# Memory_256M.net
KiCad netlist of a schematic drawn in Altium Designer
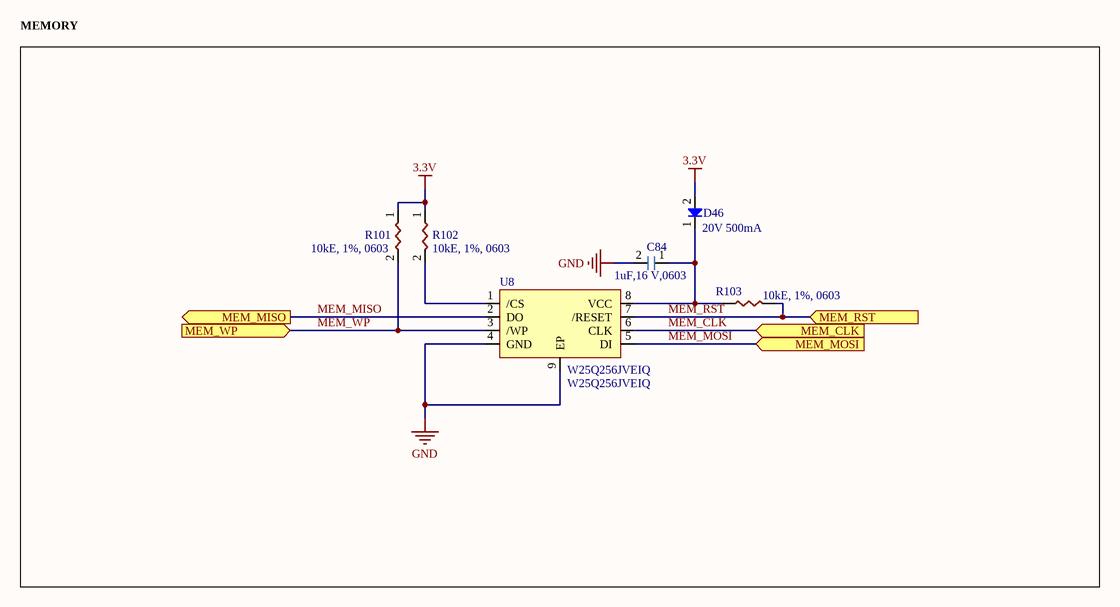
[diagram p0: Memory_256M.SchDoc]

(export (version "E")
  (design (tool "Eeschema 10.0.6"))
  (components
    (comp (ref "C84")
      (value "CGA3E1X7R1C105K080AC")
      (footprint "CAPC1608X05N 0603")
      (description "Multilayer Ceramic Capacitor, 1uF, 16V, ±10%,  X7R 0603 [1608 Metric]")
      (fields
        (field (name "MANUFACTURER") "TDK Corporation")
        (field (name "VOLTAGE") "16V")
        (field (name "VALUE DISPLAY") "1uF,16 V,0603")
      )
      (libsource (lib "BMS_V2.1_Adv") (part "Cap_CGA3E1X7R1C105K080AC"))
    )
    (comp (ref "D46")
      (value "SBR80520LT1G")
      (footprint "DIODE_SOD123")
      (description "Diode 20 V 500mA Surface Mount SOD-123")
      (fields
        (field (name "MANUFACTURER") "OnSemi")
        (field (name "VALUE DISPLAY") "20V 500mA")
        (field (name "VOLTAGE") "20V")
      )
      (libsource (lib "BMS_V2.1_Adv") (part "Diode_SBR80520LT1G"))
    )
    (comp (ref "R101")
      (value "CRCW060310K0FKEA")
      (footprint "RESC1608X05N 0603")
      (description "SMD Chip Resistor, 10 kOhm,±1%, 100 mW, 0603 [1608 Metric], Thick Film, General Purpose")
      (fields
        (field (name "MANUFACTURER") "Vishay Dale")
        (field (name "POWER") "1/10W")
        (field (name "VALUE DISPLAY") "10kE, 1%, 0603")
      )
      (libsource (lib "BMS_V2.1_Adv") (part "Res_CRCW060310K0FKEA"))
    )
    (comp (ref "R102")
      (value "CRCW060310K0FKEA")
      (footprint "RESC1608X05N 0603")
      (description "SMD Chip Resistor, 10 kOhm,±1%, 100 mW, 0603 [1608 Metric], Thick Film, General Purpose")
      (fields
        (field (name "MANUFACTURER") "Vishay Dale")
        (field (name "POWER") "1/10W")
        (field (name "VALUE DISPLAY") "10kE, 1%, 0603")
      )
      (libsource (lib "BMS_V2.1_Adv") (part "Res_CRCW060310K0FKEA"))
    )
    (comp (ref "R103")
      (value "CRCW060310K0FKEA")
      (footprint "RESC1608X05N 0603")
      (description "SMD Chip Resistor, 10 kOhm,±1%, 100 mW, 0603 [1608 Metric], Thick Film, General Purpose")
      (fields
        (field (name "MANUFACTURER") "Vishay Dale")
        (field (name "POWER") "1/10W")
        (field (name "VALUE DISPLAY") "10kE, 1%, 0603")
      )
      (libsource (lib "") (part "Res_CRCW060310K0FKEA_1"))
    )
    (comp (ref "U8")
      (value "W25Q256JVEIQ")
      (footprint "SON127P800X80_HS-9N")
      (description "FLASH - NOR Memory IC 256Mbit SPI - Quad I/O 133 MHz 8-WSON (8x6)")
      (fields
        (field (name "MANUFACTURER") "Winbond")
        (field (name "VALUE DISPLAY") "W25Q256JVEIQ")
        (field (name "VOLTAGE") "3.3V")
      )
      (libsource (lib "BMS_V2.1_Adv") (part "IC_W25Q256JVEIQ"))
    )
  )
  (nets
    (net (code "1") (name "/MEM_CLK") (class "Default")
      (node (ref "U8") (pin "6") (pinfunction "CLK_6") (pintype "passive"))
    )
    (net (code "2") (name "/MEM_MISO") (class "Default")
      (node (ref "U8") (pin "2") (pinfunction "DO_2") (pintype "passive"))
    )
    (net (code "3") (name "/MEM_MOSI") (class "Default")
      (node (ref "U8") (pin "5") (pinfunction "DI_5") (pintype "passive"))
    )
    (net (code "4") (name "/MEM_RST") (class "Default")
      (node (ref "R103") (pin "1") (pinfunction "1_1") (pintype "passive"))
      (node (ref "U8") (pin "7") (pinfunction "/RESET_7") (pintype "passive"))
    )
    (net (code "5") (name "/MEM_WP") (class "Default")
      (node (ref "R102") (pin "2") (pinfunction "2_2") (pintype "passive"))
      (node (ref "U8") (pin "3") (pinfunction "/WP_3") (pintype "passive"))
    )
    (net (code "6") (name "3.3V") (class "Default")
      (node (ref "D46") (pin "2") (pinfunction "Anode_2") (pintype "passive"))
      (node (ref "R101") (pin "1") (pinfunction "1_1") (pintype "passive"))
      (node (ref "R102") (pin "1") (pinfunction "1_1") (pintype "passive"))
    )
    (net (code "7") (name "GND") (class "Default")
      (node (ref "C84") (pin "2") (pinfunction "2_2") (pintype "passive"))
      (node (ref "U8") (pin "4") (pinfunction "GND_4") (pintype "passive"))
      (node (ref "U8") (pin "9") (pinfunction "EP_9") (pintype "passive"))
    )
    (net (code "8") (name "Net-(D46-Cathode)") (class "Default")
      (node (ref "C84") (pin "1") (pinfunction "1_1") (pintype "passive"))
      (node (ref "D46") (pin "1") (pinfunction "Cathode_1") (pintype "passive"))
      (node (ref "R103") (pin "2") (pinfunction "2_2") (pintype "passive"))
      (node (ref "U8") (pin "8") (pinfunction "VCC_8") (pintype "passive"))
    )
    (net (code "9") (name "Net-(U8-{slash}CS)") (class "Default")
      (node (ref "R101") (pin "2") (pinfunction "2_2") (pintype "passive"))
      (node (ref "U8") (pin "1") (pinfunction "/CS_1") (pintype "passive"))
    )
  )
)
